# shield.net
KiCad netlist of a schematic drawn in EAGLE
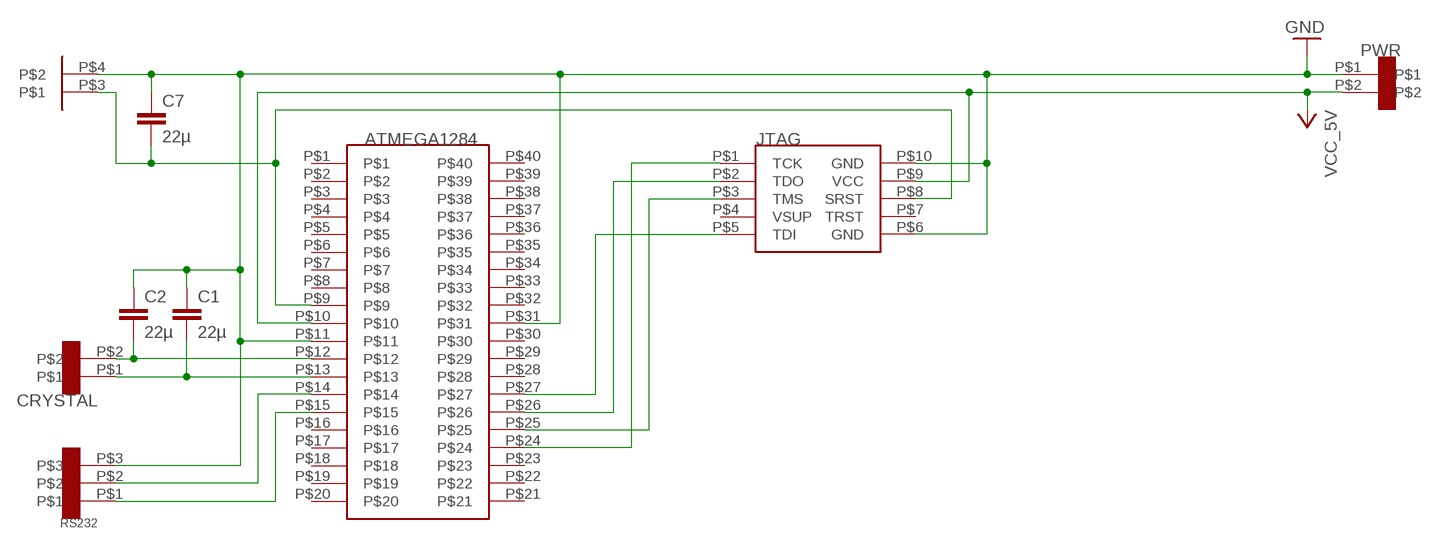
[diagram p0: schematic, sheet 1]

(export (version "E")
  (design (tool "Eeschema 10.0.6"))
  (components
    (comp (ref "ATMEGA1284")
      (value "CON_DIL_2X20")
      (footprint "eagle-import:CON_DIL_2X20")
      (libsource (lib "eagle-import") (part "CON_DIL_2X20"))
    )
    (comp (ref "C1")
      (value "22µ")
      (footprint "eagle-import:C025-030X050")
      (libsource (lib "eagle-import") (part "C-EU025-030X050"))
    )
    (comp (ref "C2")
      (value "22µ")
      (footprint "eagle-import:C025-030X050")
      (libsource (lib "eagle-import") (part "C-EU025-030X050"))
    )
    (comp (ref "C7")
      (value "22µ")
      (footprint "eagle-import:C025-030X050")
      (libsource (lib "eagle-import") (part "C-EU025-030X050"))
    )
    (comp (ref "CRYSTAL")
      (value "CON_DIL_2")
      (footprint "eagle-import:CON_DIL_2")
      (libsource (lib "eagle-import") (part "CON_DIL_2"))
    )
    (comp (ref "JTAG")
      (value "JTAG")
      (footprint "eagle-import:CON_DIL_2X5")
      (libsource (lib "eagle-import") (part "JTAG"))
    )
    (comp (ref "PWR")
      (value "CON_DIL_2")
      (footprint "eagle-import:CON_DIL_2")
      (libsource (lib "eagle-import") (part "CON_DIL_2"))
    )
    (comp (ref "RS232")
      (value "CON_DIL_3")
      (footprint "eagle-import:CON_DIL_3")
      (libsource (lib "eagle-import") (part "CON_DIL_3"))
    )
    (comp (ref "RST")
      (value "RST")
      (footprint "eagle-import:RST")
      (libsource (lib "eagle-import") (part "RST"))
    )
  )
  (nets
    (net (code "1") (name "GND") (class "Default")
      (node (ref "ATMEGA1284") (pin "P$11") (pinfunction "P$11_P$11") (pintype "bidirectional"))
      (node (ref "ATMEGA1284") (pin "P$31") (pinfunction "P$31_P$31") (pintype "bidirectional"))
      (node (ref "C1") (pin "1") (pinfunction "1_1") (pintype "passive"))
      (node (ref "C2") (pin "1") (pinfunction "1_1") (pintype "passive"))
      (node (ref "C7") (pin "1") (pinfunction "1_1") (pintype "passive"))
      (node (ref "JTAG") (pin "P$10") (pinfunction "GND_P$10") (pintype "bidirectional"))
      (node (ref "JTAG") (pin "P$6") (pinfunction "GND_P$6") (pintype "bidirectional"))
      (node (ref "PWR") (pin "P$1") (pinfunction "P$1_P$1") (pintype "bidirectional"))
      (node (ref "RS232") (pin "P$3") (pinfunction "P$3_P$3") (pintype "bidirectional"))
      (node (ref "RST") (pin "P$4") (pinfunction "P$2_P$4") (pintype "bidirectional"))
    )
    (net (code "2") (name "Net-(ATMEGA1284-PadP$12)") (class "Default")
      (node (ref "ATMEGA1284") (pin "P$12") (pinfunction "P$12_P$12") (pintype "bidirectional"))
      (node (ref "C2") (pin "2") (pinfunction "2_2") (pintype "passive"))
      (node (ref "CRYSTAL") (pin "P$2") (pinfunction "P$2_P$2") (pintype "bidirectional"))
    )
    (net (code "3") (name "Net-(ATMEGA1284-PadP$13)") (class "Default")
      (node (ref "ATMEGA1284") (pin "P$13") (pinfunction "P$13_P$13") (pintype "bidirectional"))
      (node (ref "C1") (pin "2") (pinfunction "2_2") (pintype "passive"))
      (node (ref "CRYSTAL") (pin "P$1") (pinfunction "P$1_P$1") (pintype "bidirectional"))
    )
    (net (code "4") (name "Net-(ATMEGA1284-PadP$14)") (class "Default")
      (node (ref "ATMEGA1284") (pin "P$14") (pinfunction "P$14_P$14") (pintype "bidirectional"))
      (node (ref "RS232") (pin "P$2") (pinfunction "P$2_P$2") (pintype "bidirectional"))
    )
    (net (code "5") (name "Net-(ATMEGA1284-PadP$15)") (class "Default")
      (node (ref "ATMEGA1284") (pin "P$15") (pinfunction "P$15_P$15") (pintype "bidirectional"))
      (node (ref "RS232") (pin "P$1") (pinfunction "P$1_P$1") (pintype "bidirectional"))
    )
    (net (code "6") (name "Net-(JTAG-SRST)") (class "Default")
      (node (ref "ATMEGA1284") (pin "P$9") (pinfunction "P$9_P$9") (pintype "bidirectional"))
      (node (ref "C7") (pin "2") (pinfunction "2_2") (pintype "passive"))
      (node (ref "JTAG") (pin "P$8") (pinfunction "SRST_P$8") (pintype "bidirectional"))
      (node (ref "RST") (pin "P$3") (pinfunction "P$1_P$3") (pintype "bidirectional"))
    )
    (net (code "7") (name "Net-(JTAG-TCK)") (class "Default")
      (node (ref "ATMEGA1284") (pin "P$24") (pinfunction "P$24_P$24") (pintype "bidirectional"))
      (node (ref "JTAG") (pin "P$1") (pinfunction "TCK_P$1") (pintype "bidirectional"))
    )
    (net (code "8") (name "Net-(JTAG-TDI)") (class "Default")
      (node (ref "ATMEGA1284") (pin "P$27") (pinfunction "P$27_P$27") (pintype "bidirectional"))
      (node (ref "JTAG") (pin "P$5") (pinfunction "TDI_P$5") (pintype "bidirectional"))
    )
    (net (code "9") (name "Net-(JTAG-TDO)") (class "Default")
      (node (ref "ATMEGA1284") (pin "P$26") (pinfunction "P$26_P$26") (pintype "bidirectional"))
      (node (ref "JTAG") (pin "P$2") (pinfunction "TDO_P$2") (pintype "bidirectional"))
    )
    (net (code "10") (name "Net-(JTAG-TMS)") (class "Default")
      (node (ref "ATMEGA1284") (pin "P$25") (pinfunction "P$25_P$25") (pintype "bidirectional"))
      (node (ref "JTAG") (pin "P$3") (pinfunction "TMS_P$3") (pintype "bidirectional"))
    )
    (net (code "11") (name "VCC_5V") (class "Default")
      (node (ref "ATMEGA1284") (pin "P$10") (pinfunction "P$10_P$10") (pintype "bidirectional"))
      (node (ref "JTAG") (pin "P$9") (pinfunction "VCC_P$9") (pintype "bidirectional"))
      (node (ref "PWR") (pin "P$2") (pinfunction "P$2_P$2") (pintype "bidirectional"))
    )
    (net (code "12") (name "unconnected-(ATMEGA1284-PadP$1)") (class "Default")
      (node (ref "ATMEGA1284") (pin "P$1") (pinfunction "P$1_P$1") (pintype "bidirectional"))
    )
    (net (code "13") (name "unconnected-(ATMEGA1284-PadP$2)") (class "Default")
      (node (ref "ATMEGA1284") (pin "P$2") (pinfunction "P$2_P$2") (pintype "bidirectional"))
    )
    (net (code "14") (name "unconnected-(ATMEGA1284-PadP$3)") (class "Default")
      (node (ref "ATMEGA1284") (pin "P$3") (pinfunction "P$3_P$3") (pintype "bidirectional"))
    )
    (net (code "15") (name "unconnected-(ATMEGA1284-PadP$4)") (class "Default")
      (node (ref "ATMEGA1284") (pin "P$4") (pinfunction "P$4_P$4") (pintype "bidirectional"))
    )
    (net (code "16") (name "unconnected-(ATMEGA1284-PadP$5)") (class "Default")
      (node (ref "ATMEGA1284") (pin "P$5") (pinfunction "P$5_P$5") (pintype "bidirectional"))
    )
    (net (code "17") (name "unconnected-(ATMEGA1284-PadP$6)") (class "Default")
      (node (ref "ATMEGA1284") (pin "P$6") (pinfunction "P$6_P$6") (pintype "bidirectional"))
    )
    (net (code "18") (name "unconnected-(ATMEGA1284-PadP$7)") (class "Default")
      (node (ref "ATMEGA1284") (pin "P$7") (pinfunction "P$7_P$7") (pintype "bidirectional"))
    )
    (net (code "19") (name "unconnected-(ATMEGA1284-PadP$8)") (class "Default")
      (node (ref "ATMEGA1284") (pin "P$8") (pinfunction "P$8_P$8") (pintype "bidirectional"))
    )
    (net (code "20") (name "unconnected-(ATMEGA1284-PadP$16)") (class "Default")
      (node (ref "ATMEGA1284") (pin "P$16") (pinfunction "P$16_P$16") (pintype "bidirectional"))
    )
    (net (code "21") (name "unconnected-(ATMEGA1284-PadP$17)") (class "Default")
      (node (ref "ATMEGA1284") (pin "P$17") (pinfunction "P$17_P$17") (pintype "bidirectional"))
    )
    (net (code "22") (name "unconnected-(ATMEGA1284-PadP$18)") (class "Default")
      (node (ref "ATMEGA1284") (pin "P$18") (pinfunction "P$18_P$18") (pintype "bidirectional"))
    )
    (net (code "23") (name "unconnected-(ATMEGA1284-PadP$19)") (class "Default")
      (node (ref "ATMEGA1284") (pin "P$19") (pinfunction "P$19_P$19") (pintype "bidirectional"))
    )
    (net (code "24") (name "unconnected-(ATMEGA1284-PadP$20)") (class "Default")
      (node (ref "ATMEGA1284") (pin "P$20") (pinfunction "P$20_P$20") (pintype "bidirectional"))
    )
    (net (code "25") (name "unconnected-(ATMEGA1284-PadP$21)") (class "Default")
      (node (ref "ATMEGA1284") (pin "P$21") (pinfunction "P$21_P$21") (pintype "bidirectional"))
    )
    (net (code "26") (name "unconnected-(ATMEGA1284-PadP$22)") (class "Default")
      (node (ref "ATMEGA1284") (pin "P$22") (pinfunction "P$22_P$22") (pintype "bidirectional"))
    )
    (net (code "27") (name "unconnected-(ATMEGA1284-PadP$23)") (class "Default")
      (node (ref "ATMEGA1284") (pin "P$23") (pinfunction "P$23_P$23") (pintype "bidirectional"))
    )
    (net (code "28") (name "unconnected-(ATMEGA1284-PadP$28)") (class "Default")
      (node (ref "ATMEGA1284") (pin "P$28") (pinfunction "P$28_P$28") (pintype "bidirectional"))
    )
    (net (code "29") (name "unconnected-(ATMEGA1284-PadP$29)") (class "Default")
      (node (ref "ATMEGA1284") (pin "P$29") (pinfunction "P$29_P$29") (pintype "bidirectional"))
    )
    (net (code "30") (name "unconnected-(ATMEGA1284-PadP$30)") (class "Default")
      (node (ref "ATMEGA1284") (pin "P$30") (pinfunction "P$30_P$30") (pintype "bidirectional"))
    )
    (net (code "31") (name "unconnected-(ATMEGA1284-PadP$32)") (class "Default")
      (node (ref "ATMEGA1284") (pin "P$32") (pinfunction "P$32_P$32") (pintype "bidirectional"))
    )
    (net (code "32") (name "unconnected-(ATMEGA1284-PadP$33)") (class "Default")
      (node (ref "ATMEGA1284") (pin "P$33") (pinfunction "P$33_P$33") (pintype "bidirectional"))
    )
    (net (code "33") (name "unconnected-(ATMEGA1284-PadP$34)") (class "Default")
      (node (ref "ATMEGA1284") (pin "P$34") (pinfunction "P$34_P$34") (pintype "bidirectional"))
    )
    (net (code "34") (name "unconnected-(ATMEGA1284-PadP$35)") (class "Default")
      (node (ref "ATMEGA1284") (pin "P$35") (pinfunction "P$35_P$35") (pintype "bidirectional"))
    )
    (net (code "35") (name "unconnected-(ATMEGA1284-PadP$36)") (class "Default")
      (node (ref "ATMEGA1284") (pin "P$36") (pinfunction "P$36_P$36") (pintype "bidirectional"))
    )
    (net (code "36") (name "unconnected-(ATMEGA1284-PadP$37)") (class "Default")
      (node (ref "ATMEGA1284") (pin "P$37") (pinfunction "P$37_P$37") (pintype "bidirectional"))
    )
    (net (code "37") (name "unconnected-(ATMEGA1284-PadP$38)") (class "Default")
      (node (ref "ATMEGA1284") (pin "P$38") (pinfunction "P$38_P$38") (pintype "bidirectional"))
    )
    (net (code "38") (name "unconnected-(ATMEGA1284-PadP$39)") (class "Default")
      (node (ref "ATMEGA1284") (pin "P$39") (pinfunction "P$39_P$39") (pintype "bidirectional"))
    )
    (net (code "39") (name "unconnected-(ATMEGA1284-PadP$40)") (class "Default")
      (node (ref "ATMEGA1284") (pin "P$40") (pinfunction "P$40_P$40") (pintype "bidirectional"))
    )
    (net (code "40") (name "unconnected-(JTAG-TRST-PadP$7)") (class "Default")
      (node (ref "JTAG") (pin "P$7") (pinfunction "TRST_P$7") (pintype "bidirectional"))
    )
    (net (code "41") (name "unconnected-(JTAG-VSUP-PadP$4)") (class "Default")
      (node (ref "JTAG") (pin "P$4") (pinfunction "VSUP_P$4") (pintype "bidirectional"))
    )
  )
)
